# SCH__UPS__2024-01-14.net
KiCad netlist of a schematic drawn in EasyEDA
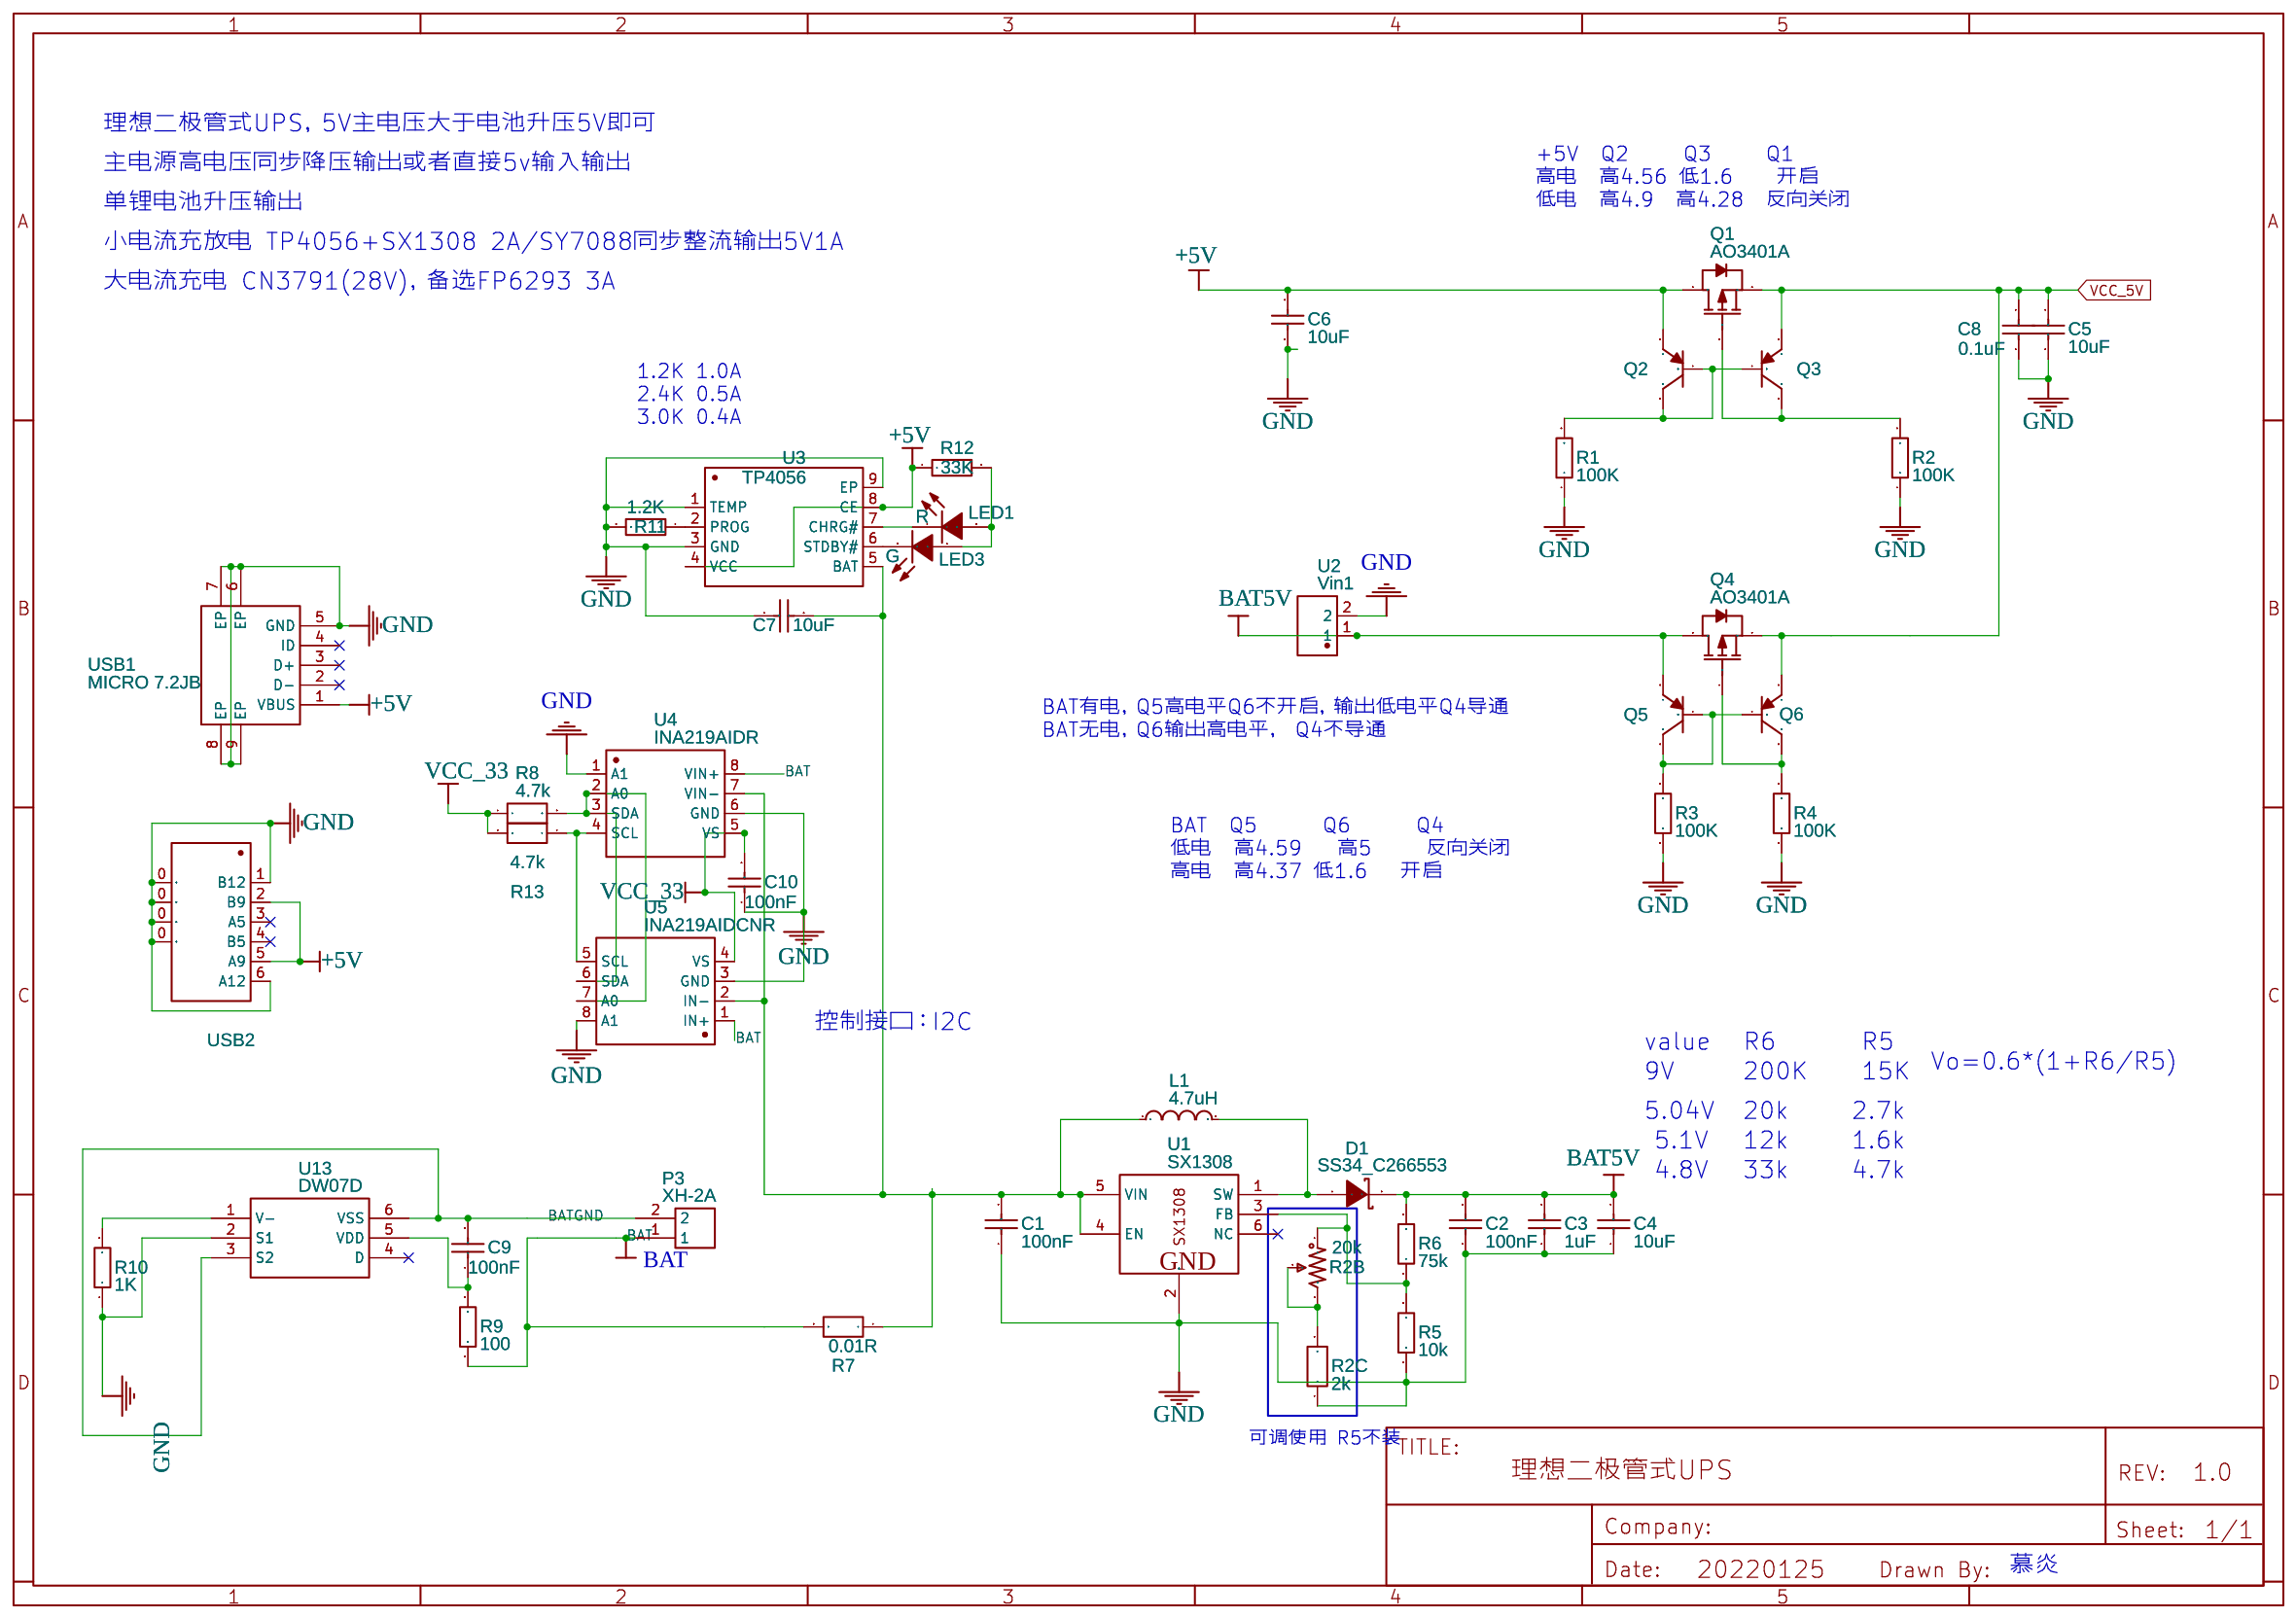
[diagram p0: schematic sheet]

(export (version "E")
  (design (tool "Eeschema 10.0.6"))
  (components
    (comp (ref "C1")
      (value "100nF")
      (fields (field (name "Manufacturer Part") "CC0402KRX7R9BB104") (field (name "Manufacturer") "YAGEO"))
      (libsource (lib "") (part "CC0402KRX7R9BB104"))
    )
    (comp (ref "C2")
      (value "100nF")
      (fields (field (name "Manufacturer Part") "CC0402KRX7R9BB104") (field (name "Manufacturer") "YAGEO"))
      (libsource (lib "") (part "CC0402KRX7R9BB104"))
    )
    (comp (ref "C3")
      (value "1uF")
      (fields (field (name "Manufacturer Part") "CL05A105KO5NNNC") (field (name "Manufacturer") "SAMSUNG"))
      (libsource (lib "") (part "CL05A105KO5NNNC"))
    )
    (comp (ref "C4")
      (value "10uF")
      (fields (field (name "Manufacturer Part") "CL10A106MO8NQNC") (field (name "Manufacturer") "SAMSUNG"))
      (libsource (lib "") (part "CL10A106MO8NQNC"))
    )
    (comp (ref "C5")
      (value "10uF")
      (fields (field (name "Manufacturer Part") "CL10A106MO8NQNC") (field (name "Manufacturer") "SAMSUNG"))
      (libsource (lib "") (part "CL10A106MO8NQNC"))
    )
    (comp (ref "C6")
      (value "10uF")
      (fields (field (name "Manufacturer Part") "CL10A106MO8NQNC") (field (name "Manufacturer") "SAMSUNG"))
      (libsource (lib "") (part "CL10A106MO8NQNC"))
    )
    (comp (ref "C7")
      (value "10uF")
      (fields
        (field (name "Manufacturer Part") "GRM21BB31C106KE15L")
        (field (name "Manufacturer") "Murata Electronics")
      )
      (libsource (lib "") (part "GRM21BB31C106KE15L"))
    )
    (comp (ref "C8")
      (value "0.1uF")
      (fields (field (name "Manufacturer Part") "CL10A106MO8NQNC") (field (name "Manufacturer") "SAMSUNG"))
      (libsource (lib "") (part "CL10A106MO8NQNC"))
    )
    (comp (ref "C9")
      (value "100nF")
      (fields (field (name "Manufacturer Part") "CL05B104KO5NNNC") (field (name "Manufacturer") "SAMSUNG"))
      (libsource (lib "") (part "CL05B104KO5NNNC"))
    )
    (comp (ref "C10")
      (value "100nF")
      (fields (field (name "Manufacturer Part") "CL05B104KO5NNNC") (field (name "Manufacturer") "SAMSUNG"))
      (libsource (lib "") (part "CL05B104KO5NNNC"))
    )
    (comp (ref "D1")
      (value "SS34_C266553")
      (fields
        (field (name "Manufacturer Part") "SS34")
        (field (name "Manufacturer") "Bourne Semicon (Shenzhen)")
      )
      (libsource (lib "") (part "Unknown_680_598"))
    )
    (comp (ref "L1")
      (value "4.7uH")
      (fields
        (field (name "Manufacturer Part") "SLO0630H330MTT")
        (field (name "Manufacturer") "Sunltech Tech")
      )
      (libsource (lib "") (part "SLO0630H330MTT"))
    )
    (comp (ref "LED1")
      (value "R")
      (fields (field (name "Manufacturer Part") "FC-2012HRK-620D") (field (name "Manufacturer") "NATIONSTAR"))
      (libsource (lib "") (part "FC-2012HRK-620D"))
    )
    (comp (ref "LED3")
      (value "G")
      (fields
        (field (name "Manufacturer Part") "TJ-S2012SW8TGLC2G-A5")
        (field (name "Manufacturer") "TOGIALED")
      )
      (libsource (lib "") (part "TJ-S2012SW8TGLC2G-A5"))
    )
    (comp (ref "P3")
      (value "XH-2A")
      (fields (field (name "Manufacturer") "BOOMELE"))
      (libsource (lib "") (part "Unknown_335_615"))
    )
    (comp (ref "Q1")
      (value "AO3401A")
      (fields (field (name "Manufacturer") "AOS"))
      (libsource (lib "") (part "Unknown_865_150"))
    )
    (comp (ref "Q2")
      (value "BCW68GLT1G")
      (fields (field (name "Manufacturer") "ON"))
      (libsource (lib "") (part "Unknown_845_180"))
    )
    (comp (ref "Q3")
      (value "BCW68GLT1G")
      (fields (field (name "Manufacturer") "ON"))
      (libsource (lib "") (part "Unknown_885_180"))
    )
    (comp (ref "Q4")
      (value "AO3401A")
      (fields (field (name "Manufacturer") "AOS"))
      (libsource (lib "") (part "Unknown_865_325"))
    )
    (comp (ref "Q5")
      (value "BCW68GLT1G")
      (fields (field (name "Manufacturer") "ON"))
      (libsource (lib "") (part "Unknown_845_355"))
    )
    (comp (ref "Q6")
      (value "BCW68GLT1G")
      (fields (field (name "Manufacturer") "ON"))
      (libsource (lib "") (part "Unknown_885_355"))
    )
    (comp (ref "R1")
      (value "100K")
      (fields (field (name "Manufacturer Part") "0402WGF1003TCE") (field (name "Manufacturer") "UniOhm"))
      (libsource (lib "") (part "0402WGF1003TCE"))
    )
    (comp (ref "R2")
      (value "100K")
      (fields (field (name "Manufacturer Part") "0402WGF1003TCE") (field (name "Manufacturer") "UniOhm"))
      (libsource (lib "") (part "0402WGF1003TCE"))
    )
    (comp (ref "R2B")
      (value "20k")
      (fields
        (field (name "Manufacturer Part") "3296W-1-103")
        (field (name "Manufacturer") "Chengdu Guosheng Tech")
      )
      (libsource (lib "") (part "3296W-1-103"))
    )
    (comp (ref "R2C") (value "2k") (libsource (lib "") (part "R_0603_EU")))
    (comp (ref "R3")
      (value "100K")
      (fields (field (name "Manufacturer Part") "0402WGF1003TCE") (field (name "Manufacturer") "UniOhm"))
      (libsource (lib "") (part "0402WGF1003TCE"))
    )
    (comp (ref "R4")
      (value "100K")
      (fields (field (name "Manufacturer Part") "0402WGF1003TCE") (field (name "Manufacturer") "UniOhm"))
      (libsource (lib "") (part "0402WGF1003TCE"))
    )
    (comp (ref "R5")
      (value "10k")
      (fields (field (name "Manufacturer Part") "0402WGJ0102TCE") (field (name "Manufacturer") "UniOhm"))
      (libsource (lib "") (part "0402WGJ0102TCE"))
    )
    (comp (ref "R6")
      (value "75k")
      (fields (field (name "Manufacturer Part") "RTT021402FTH") (field (name "Manufacturer") "RALEC"))
      (libsource (lib "") (part "RTT021402FTH"))
    )
    (comp (ref "R7") (value "0.01R") (libsource (lib "") (part "R_0805_EU_1")))
    (comp (ref "R8") (value "4.7k") (libsource (lib "") (part "R_0805_EU")))
    (comp (ref "R9")
      (value "100")
      (fields (field (name "Manufacturer Part") "AC0402JR-07100RL") (field (name "Manufacturer") "YAGEO"))
      (libsource (lib "") (part "AC0402JR-07100RL"))
    )
    (comp (ref "R10")
      (value "1K")
      (fields (field (name "Manufacturer Part") "RMC04021K1%N") (field (name "Manufacturer") "Tyohm"))
      (libsource (lib "") (part "RMC04021K1%N"))
    )
    (comp (ref "R11")
      (value "1.2K")
      (fields (field (name "Manufacturer Part") "RMC06031.2K1%N") (field (name "Manufacturer") "Tyohm"))
      (libsource (lib "") (part "RMC06031.2K1%N"))
    )
    (comp (ref "R12")
      (value "33K")
      (fields (field (name "Manufacturer Part") "RMC06031K1%N") (field (name "Manufacturer") "Tyohm"))
      (libsource (lib "") (part "RMC06031K1%N"))
    )
    (comp (ref "R13") (value "4.7k") (libsource (lib "") (part "R_0805_EU_1")))
    (comp (ref "U1")
      (value "SX1308")
      (fields (field (name "Manufacturer") "SX"))
      (libsource (lib "") (part "Unknown_590_623"))
    )
    (comp (ref "U2")
      (value "Vin1")
      (fields
        (field (name "Manufacturer Part") "KF127-5.08-2P")
        (field (name "Manufacturer") "Cixi Kefa Elec")
      )
      (libsource (lib "") (part "KF127-5.08-2P"))
    )
    (comp (ref "U3")
      (value "TP4056")
      (fields (field (name "Manufacturer") "TPOWER"))
      (libsource (lib "") (part "TP4056_C382139"))
    )
    (comp (ref "U4")
      (value "INA219AIDR")
      (fields (field (name "Manufacturer") "TI"))
      (libsource (lib "") (part "INA219AIDR"))
    )
    (comp (ref "U5")
      (value "INA219AIDCNR")
      (fields (field (name "Manufacturer") "TI"))
      (libsource (lib "") (part "INA219AIDCNR"))
    )
    (comp (ref "U13")
      (value "DW07D")
      (fields (field (name "Manufacturer") "FM"))
      (libsource (lib "") (part "Unknown_150_620"))
    )
    (comp (ref "USB1")
      (value "MICRO 7.2JB")
      (fields (field (name "Manufacturer") "SHOU HAN(首韩)"))
      (libsource (lib "") (part "MICRO 7.2JB"))
    )
    (comp (ref "USB2")
      (value "TYPE-C-31-M-17")
      (fields (field (name "Manufacturer") "Korean Hroparts Elec"))
      (libsource (lib "") (part "TYPE-C-31-M-17"))
    )
  )
  (nets
    (net (code "1") (name "+5V") (class "Default")
      (node (ref "C6") (pin "2") (pinfunction "2_2") (pintype "input"))
      (node (ref "Q1") (pin "3") (pinfunction "D_3") (pintype "unspecified"))
      (node (ref "Q2") (pin "2") (pinfunction "E_2") (pintype "unspecified"))
      (node (ref "R12") (pin "1") (pinfunction "1_1") (pintype "unspecified"))
      (node (ref "U3") (pin "4") (pinfunction "VCC_4") (pintype "unspecified"))
      (node (ref "U3") (pin "8") (pinfunction "CE_8") (pintype "unspecified"))
      (node (ref "USB1") (pin "1") (pinfunction "VBUS_1") (pintype "unspecified"))
      (node (ref "USB2") (pin "2") (pinfunction "B9_2") (pintype "unspecified"))
      (node (ref "USB2") (pin "5") (pinfunction "A9_5") (pintype "unspecified"))
    )
    (net (code "2") (name "/BATGND") (class "Default")
      (node (ref "C9") (pin "2") (pinfunction "2_2") (pintype "input"))
      (node (ref "P3") (pin "2") (pinfunction "2_2") (pintype "unspecified"))
      (node (ref "U13") (pin "3") (pinfunction "S2_3") (pintype "unspecified"))
      (node (ref "U13") (pin "6") (pinfunction "VSS_6") (pintype "unspecified"))
    )
    (net (code "3") (name "BAT") (class "Default")
      (node (ref "P3") (pin "1") (pinfunction "1_1") (pintype "unspecified"))
      (node (ref "R7") (pin "2") (pinfunction "2_2") (pintype "unspecified"))
      (node (ref "R9") (pin "1") (pinfunction "1_1") (pintype "input"))
      (node (ref "U4") (pin "8") (pinfunction "VIN+_8") (pintype "unspecified"))
      (node (ref "U5") (pin "1") (pinfunction "IN+_1") (pintype "unspecified"))
    )
    (net (code "4") (name "BAT5V") (class "Default")
      (node (ref "C2") (pin "2") (pinfunction "2_2") (pintype "input"))
      (node (ref "C3") (pin "2") (pinfunction "2_2") (pintype "input"))
      (node (ref "C4") (pin "2") (pinfunction "2_2") (pintype "input"))
      (node (ref "D1") (pin "2") (pinfunction "K_2") (pintype "unspecified"))
      (node (ref "Q4") (pin "3") (pinfunction "D_3") (pintype "unspecified"))
      (node (ref "Q5") (pin "2") (pinfunction "E_2") (pintype "unspecified"))
      (node (ref "R6") (pin "2") (pinfunction "2_2") (pintype "input"))
      (node (ref "U2") (pin "1") (pinfunction "1_1") (pintype "unspecified"))
    )
    (net (code "5") (name "GND") (class "Default")
      (node (ref "C1") (pin "1") (pinfunction "1_1") (pintype "input"))
      (node (ref "C10") (pin "1") (pinfunction "1_1") (pintype "input"))
      (node (ref "C2") (pin "1") (pinfunction "1_1") (pintype "input"))
      (node (ref "C3") (pin "1") (pinfunction "1_1") (pintype "input"))
      (node (ref "C4") (pin "1") (pinfunction "1_1") (pintype "input"))
      (node (ref "C5") (pin "1") (pinfunction "1_1") (pintype "input"))
      (node (ref "C6") (pin "1") (pinfunction "1_1") (pintype "input"))
      (node (ref "C7") (pin "1") (pinfunction "1_1") (pintype "input"))
      (node (ref "C8") (pin "1") (pinfunction "1_1") (pintype "input"))
      (node (ref "R1") (pin "1") (pinfunction "1_1") (pintype "input"))
      (node (ref "R10") (pin "1") (pinfunction "1_1") (pintype "unspecified"))
      (node (ref "R11") (pin "2") (pinfunction "2_2") (pintype "unspecified"))
      (node (ref "R2") (pin "1") (pinfunction "1_1") (pintype "input"))
      (node (ref "R2C") (pin "1") (pinfunction "1_1") (pintype "unspecified"))
      (node (ref "R3") (pin "1") (pinfunction "1_1") (pintype "input"))
      (node (ref "R4") (pin "1") (pinfunction "1_1") (pintype "input"))
      (node (ref "R5") (pin "1") (pinfunction "1_1") (pintype "input"))
      (node (ref "U1") (pin "2") (pinfunction "GND_2") (pintype "passive"))
      (node (ref "U13") (pin "2") (pinfunction "S1_2") (pintype "unspecified"))
      (node (ref "U2") (pin "2") (pinfunction "2_2") (pintype "unspecified"))
      (node (ref "U3") (pin "1") (pinfunction "TEMP_1") (pintype "unspecified"))
      (node (ref "U3") (pin "3") (pinfunction "GND_3") (pintype "unspecified"))
      (node (ref "U3") (pin "9") (pinfunction "EP_9") (pintype "unspecified"))
      (node (ref "U4") (pin "1") (pinfunction "A1_1") (pintype "unspecified"))
      (node (ref "U4") (pin "6") (pinfunction "GND_6") (pintype "unspecified"))
      (node (ref "U5") (pin "3") (pinfunction "GND_3") (pintype "unspecified"))
      (node (ref "U5") (pin "8") (pinfunction "A1_8") (pintype "unspecified"))
      (node (ref "USB1") (pin "5") (pinfunction "GND_5") (pintype "unspecified"))
      (node (ref "USB1") (pin "6") (pinfunction "EP_6") (pintype "unspecified"))
      (node (ref "USB1") (pin "7") (pinfunction "EP_7") (pintype "unspecified"))
      (node (ref "USB1") (pin "8") (pinfunction "EP_8") (pintype "unspecified"))
      (node (ref "USB1") (pin "9") (pinfunction "EP_9") (pintype "unspecified"))
      (node (ref "USB2") (pin "0") (pinfunction "0_0") (pintype "unspecified"))
      (node (ref "USB2") (pin "1") (pinfunction "B12_1") (pintype "unspecified"))
      (node (ref "USB2") (pin "6") (pinfunction "A12_6") (pintype "unspecified"))
    )
    (net (code "6") (name "Net-(D1-A)") (class "Default")
      (node (ref "D1") (pin "1") (pinfunction "A_1") (pintype "unspecified"))
      (node (ref "L1") (pin "2") (pinfunction "2_2") (pintype "unspecified"))
      (node (ref "U1") (pin "1") (pinfunction "SW_1") (pintype "passive"))
    )
    (net (code "7") (name "Net-(LED1-+)") (class "Default")
      (node (ref "LED1") (pin "2") (pinfunction "+_2") (pintype "unspecified"))
      (node (ref "LED3") (pin "1") (pinfunction "A_1") (pintype "unspecified"))
      (node (ref "R12") (pin "2") (pinfunction "2_2") (pintype "unspecified"))
    )
    (net (code "8") (name "Net-(LED1--)") (class "Default")
      (node (ref "LED1") (pin "1") (pinfunction "-_1") (pintype "unspecified"))
      (node (ref "U3") (pin "7") (pinfunction "CHRG#_7") (pintype "unspecified"))
    )
    (net (code "9") (name "Net-(LED3-K)") (class "Default")
      (node (ref "LED3") (pin "2") (pinfunction "K_2") (pintype "unspecified"))
      (node (ref "U3") (pin "6") (pinfunction "STDBY#_6") (pintype "unspecified"))
    )
    (net (code "10") (name "Net-(Q1-G)") (class "Default")
      (node (ref "Q1") (pin "1") (pinfunction "G_1") (pintype "unspecified"))
      (node (ref "Q3") (pin "3") (pinfunction "C_3") (pintype "unspecified"))
      (node (ref "R2") (pin "2") (pinfunction "2_2") (pintype "input"))
    )
    (net (code "11") (name "Net-(Q2-B)") (class "Default")
      (node (ref "Q2") (pin "1") (pinfunction "B_1") (pintype "unspecified"))
      (node (ref "Q2") (pin "3") (pinfunction "C_3") (pintype "unspecified"))
      (node (ref "Q3") (pin "1") (pinfunction "B_1") (pintype "unspecified"))
      (node (ref "R1") (pin "2") (pinfunction "2_2") (pintype "input"))
    )
    (net (code "12") (name "Net-(Q4-G)") (class "Default")
      (node (ref "Q4") (pin "1") (pinfunction "G_1") (pintype "unspecified"))
      (node (ref "Q6") (pin "3") (pinfunction "C_3") (pintype "unspecified"))
      (node (ref "R4") (pin "2") (pinfunction "2_2") (pintype "input"))
    )
    (net (code "13") (name "Net-(Q5-B)") (class "Default")
      (node (ref "Q5") (pin "1") (pinfunction "B_1") (pintype "unspecified"))
      (node (ref "Q5") (pin "3") (pinfunction "C_3") (pintype "unspecified"))
      (node (ref "Q6") (pin "1") (pinfunction "B_1") (pintype "unspecified"))
      (node (ref "R3") (pin "2") (pinfunction "2_2") (pintype "input"))
    )
    (net (code "14") (name "Net-(R2B-Pad2)") (class "Default")
      (node (ref "R2B") (pin "2") (pinfunction "2_2") (pintype "unspecified"))
      (node (ref "R2B") (pin "3") (pinfunction "3_3") (pintype "unspecified"))
      (node (ref "R2C") (pin "2") (pinfunction "2_2") (pintype "unspecified"))
    )
    (net (code "15") (name "Net-(U1-EN)") (class "Default")
      (node (ref "C1") (pin "2") (pinfunction "2_2") (pintype "input"))
      (node (ref "C7") (pin "2") (pinfunction "2_2") (pintype "input"))
      (node (ref "L1") (pin "1") (pinfunction "1_1") (pintype "unspecified"))
      (node (ref "R7") (pin "1") (pinfunction "1_1") (pintype "unspecified"))
      (node (ref "U1") (pin "4") (pinfunction "EN_4") (pintype "unspecified"))
      (node (ref "U1") (pin "5") (pinfunction "VIN_5") (pintype "passive"))
      (node (ref "U3") (pin "5") (pinfunction "BAT_5") (pintype "unspecified"))
      (node (ref "U4") (pin "7") (pinfunction "VIN-_7") (pintype "unspecified"))
      (node (ref "U5") (pin "2") (pinfunction "IN-_2") (pintype "unspecified"))
    )
    (net (code "16") (name "Net-(U1-FB)") (class "Default")
      (node (ref "R2B") (pin "1") (pinfunction "1_1") (pintype "unspecified"))
      (node (ref "R5") (pin "2") (pinfunction "2_2") (pintype "input"))
      (node (ref "R6") (pin "1") (pinfunction "1_1") (pintype "input"))
      (node (ref "U1") (pin "3") (pinfunction "FB_3") (pintype "unspecified"))
    )
    (net (code "17") (name "Net-(U3-PROG)") (class "Default")
      (node (ref "R11") (pin "1") (pinfunction "1_1") (pintype "unspecified"))
      (node (ref "U3") (pin "2") (pinfunction "PROG_2") (pintype "unspecified"))
    )
    (net (code "18") (name "Net-(U4-A0)") (class "Default")
      (node (ref "R8") (pin "2") (pinfunction "2_2") (pintype "unspecified"))
      (node (ref "U4") (pin "2") (pinfunction "A0_2") (pintype "unspecified"))
      (node (ref "U4") (pin "3") (pinfunction "SDA_3") (pintype "unspecified"))
      (node (ref "U5") (pin "6") (pinfunction "SDA_6") (pintype "unspecified"))
      (node (ref "U5") (pin "7") (pinfunction "A0_7") (pintype "unspecified"))
    )
    (net (code "19") (name "Net-(U4-SCL)") (class "Default")
      (node (ref "R13") (pin "1") (pinfunction "1_1") (pintype "unspecified"))
      (node (ref "U4") (pin "4") (pinfunction "SCL_4") (pintype "unspecified"))
      (node (ref "U5") (pin "5") (pinfunction "SCL_5") (pintype "unspecified"))
    )
    (net (code "20") (name "Net-(U13-V-)") (class "Default")
      (node (ref "R10") (pin "2") (pinfunction "2_2") (pintype "unspecified"))
      (node (ref "U13") (pin "1") (pinfunction "V-_1") (pintype "unspecified"))
    )
    (net (code "21") (name "Net-(U13-VDD)") (class "Default")
      (node (ref "C9") (pin "1") (pinfunction "1_1") (pintype "input"))
      (node (ref "R9") (pin "2") (pinfunction "2_2") (pintype "input"))
      (node (ref "U13") (pin "5") (pinfunction "VDD_5") (pintype "unspecified"))
    )
    (net (code "22") (name "VCC_5V") (class "Default")
      (node (ref "C5") (pin "2") (pinfunction "2_2") (pintype "input"))
      (node (ref "C8") (pin "2") (pinfunction "2_2") (pintype "input"))
      (node (ref "Q1") (pin "2") (pinfunction "S_2") (pintype "unspecified"))
      (node (ref "Q3") (pin "2") (pinfunction "E_2") (pintype "unspecified"))
      (node (ref "Q4") (pin "2") (pinfunction "S_2") (pintype "unspecified"))
      (node (ref "Q6") (pin "2") (pinfunction "E_2") (pintype "unspecified"))
    )
    (net (code "23") (name "VCC_33") (class "Default")
      (node (ref "C10") (pin "2") (pinfunction "2_2") (pintype "input"))
      (node (ref "R13") (pin "2") (pinfunction "2_2") (pintype "unspecified"))
      (node (ref "R8") (pin "1") (pinfunction "1_1") (pintype "unspecified"))
      (node (ref "U4") (pin "5") (pinfunction "VS_5") (pintype "unspecified"))
      (node (ref "U5") (pin "4") (pinfunction "VS_4") (pintype "unspecified"))
    )
    (net (code "24") (name "unconnected-(U1-NC-Pad6)") (class "Default")
      (node (ref "U1") (pin "6") (pinfunction "NC_6") (pintype "unspecified+no_connect"))
    )
    (net (code "25") (name "unconnected-(U13-D-Pad4)") (class "Default")
      (node (ref "U13") (pin "4") (pinfunction "D_4") (pintype "unspecified+no_connect"))
    )
    (net (code "26") (name "unconnected-(USB1-D+-Pad3)") (class "Default")
      (node (ref "USB1") (pin "3") (pinfunction "D+_3") (pintype "unspecified+no_connect"))
    )
    (net (code "27") (name "unconnected-(USB1-D--Pad2)") (class "Default")
      (node (ref "USB1") (pin "2") (pinfunction "D-_2") (pintype "unspecified+no_connect"))
    )
    (net (code "28") (name "unconnected-(USB1-ID-Pad4)") (class "Default")
      (node (ref "USB1") (pin "4") (pinfunction "ID_4") (pintype "unspecified+no_connect"))
    )
    (net (code "29") (name "unconnected-(USB2-A5-Pad3)") (class "Default")
      (node (ref "USB2") (pin "3") (pinfunction "A5_3") (pintype "unspecified+no_connect"))
    )
    (net (code "30") (name "unconnected-(USB2-B5-Pad4)") (class "Default")
      (node (ref "USB2") (pin "4") (pinfunction "B5_4") (pintype "unspecified+no_connect"))
    )
  )
)
